# Y1BVER2_0.net
KiCad netlist of a schematic drawn in Altium Designer
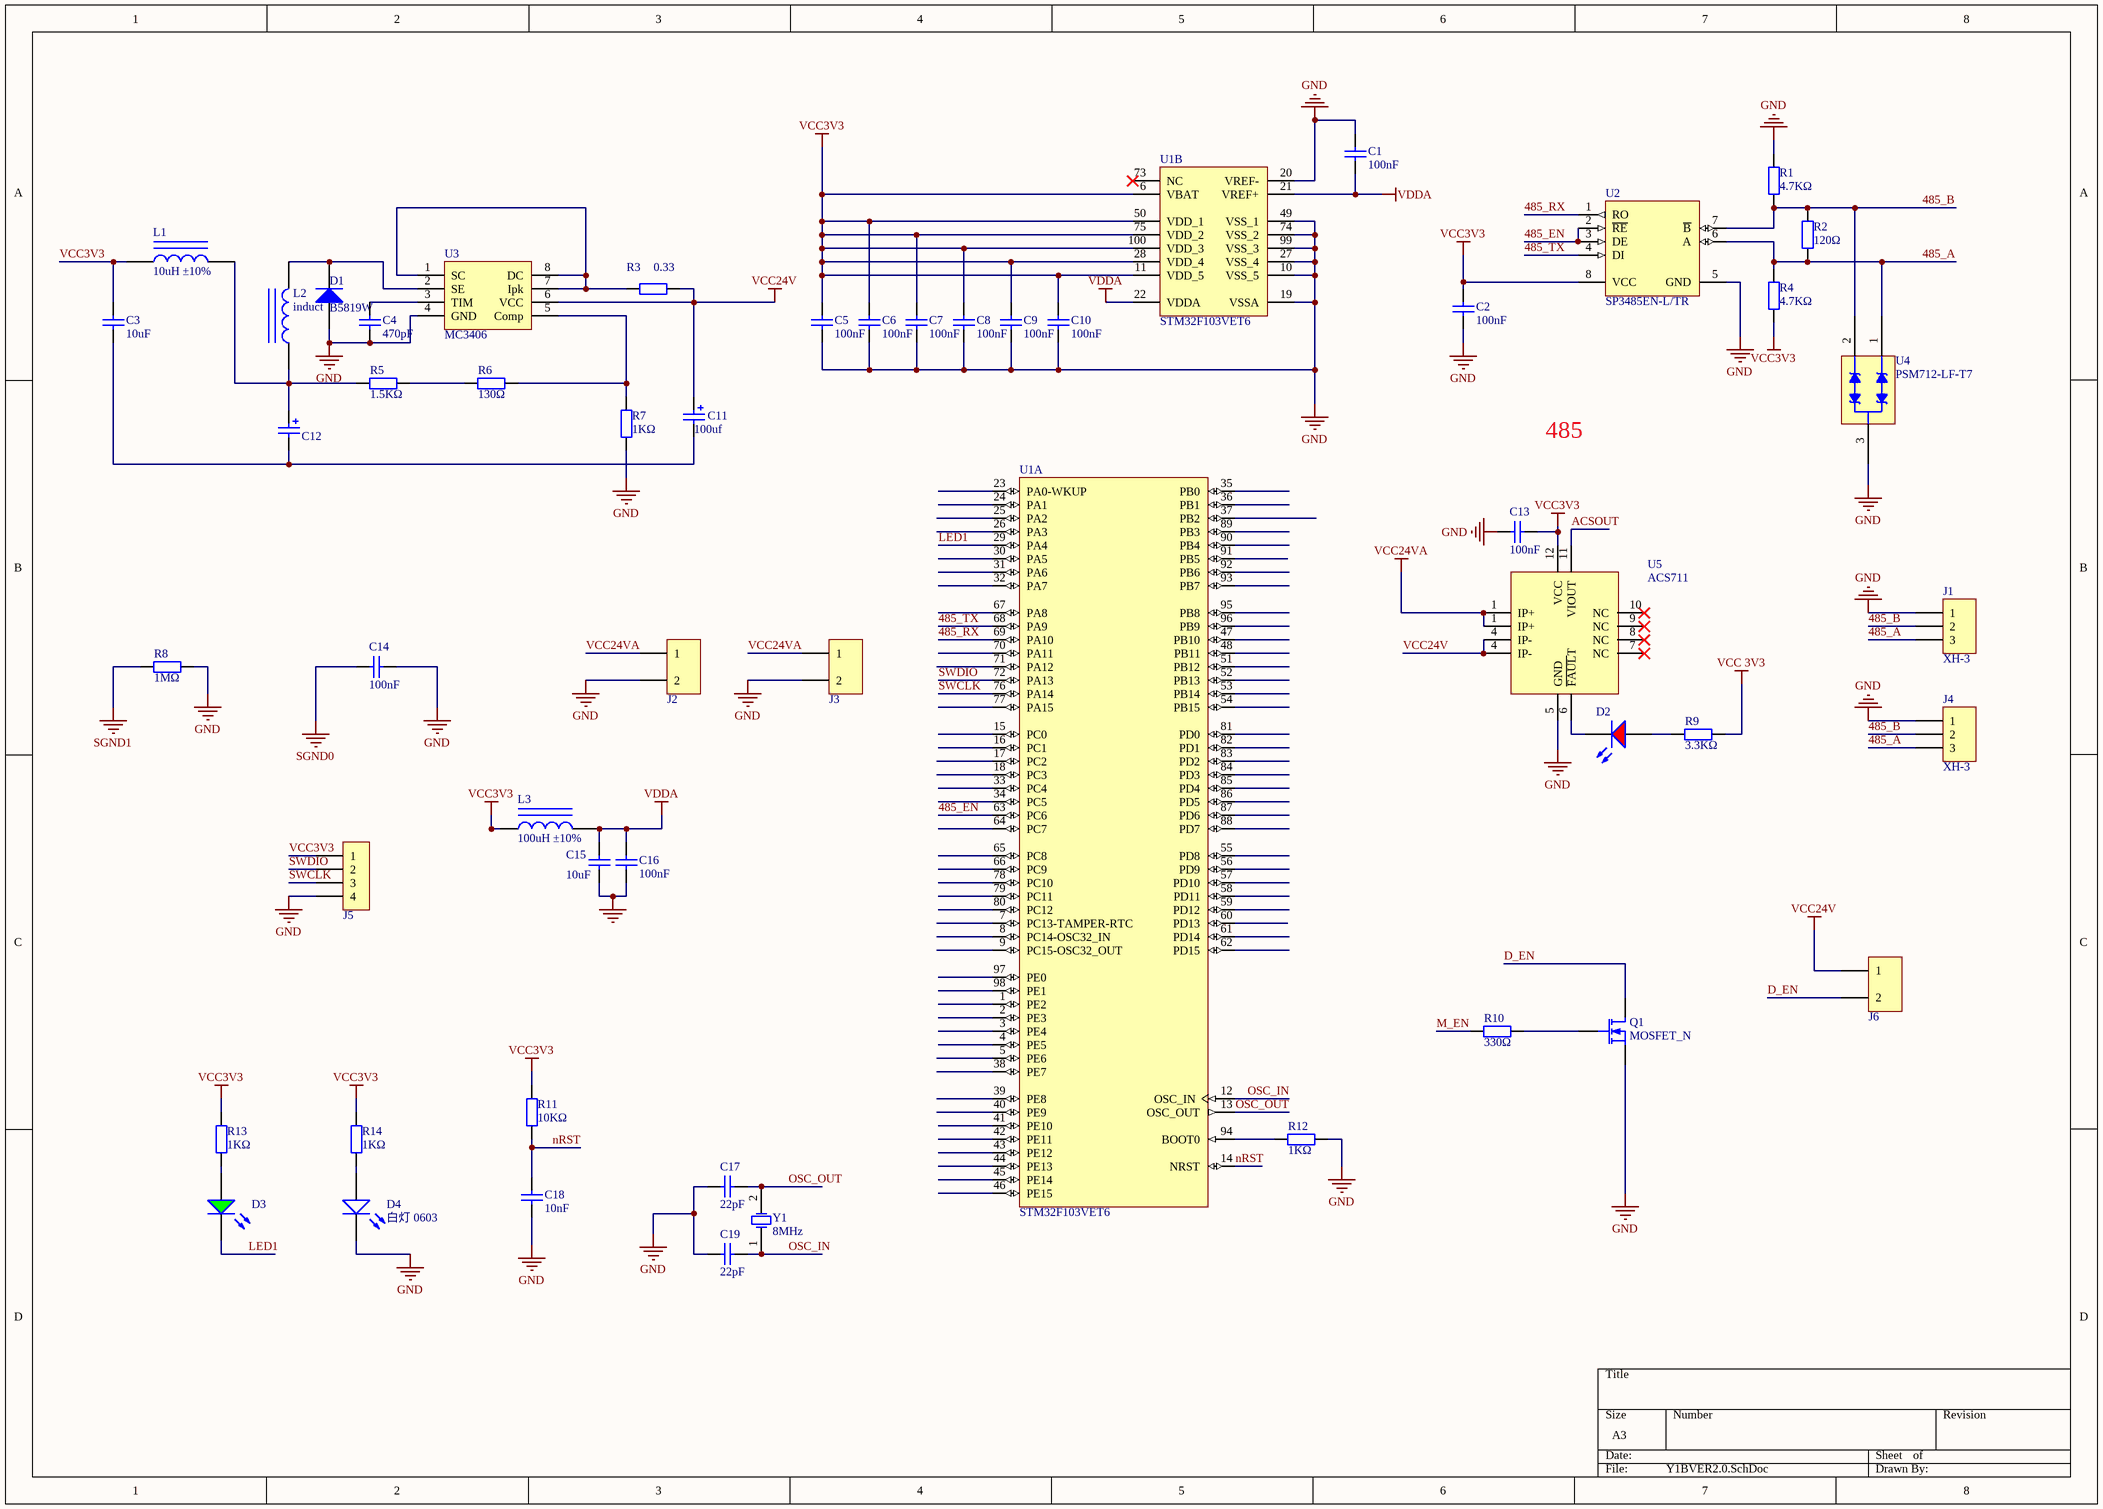
[diagram p0: Y1BVER2.0.SchDoc]

(export (version "E")
  (design (tool "Eeschema 10.0.6"))
  (components
    (comp (ref "C1")
      (value "100nF")
      (footprint "0603_C")
      (description "贴片电容")
      (libsource (lib "AD封装2018.9.19Miscellaneous Devices LC") (part "0603 100nF (104) 10% 50V"))
    )
    (comp (ref "C2")
      (value "100nF")
      (footprint "0603_C")
      (description "贴片电容")
      (libsource (lib "AD封装2018.9.19Miscellaneous Devices LC") (part "0603 100nF (104) 10% 50V"))
    )
    (comp (ref "C3")
      (value "10uF")
      (footprint "0603_C")
      (description "贴片电容")
      (libsource (lib "AD封装2018.9.19Miscellaneous Devices LC") (part "0603 10uF (106) 10% 10V"))
    )
    (comp (ref "C4")
      (value "470pF")
      (footprint "0603_C")
      (description "贴片电容")
      (libsource (lib "AD封装2018.9.19Miscellaneous Devices LC") (part "0603 470pF (471) 10% 50V"))
    )
    (comp (ref "C5")
      (value "100nF")
      (footprint "0603_C")
      (description "贴片电容")
      (libsource (lib "AD封装2018.9.19Miscellaneous Devices LC") (part "0603 100nF (104) 10% 50V"))
    )
    (comp (ref "C6")
      (value "100nF")
      (footprint "0603_C")
      (description "贴片电容")
      (libsource (lib "AD封装2018.9.19Miscellaneous Devices LC") (part "0603 100nF (104) 10% 50V"))
    )
    (comp (ref "C7")
      (value "100nF")
      (footprint "0603_C")
      (description "贴片电容")
      (libsource (lib "AD封装2018.9.19Miscellaneous Devices LC") (part "0603 100nF (104) 10% 50V"))
    )
    (comp (ref "C8")
      (value "100nF")
      (footprint "0603_C")
      (description "贴片电容")
      (libsource (lib "AD封装2018.9.19Miscellaneous Devices LC") (part "0603 100nF (104) 10% 50V"))
    )
    (comp (ref "C9")
      (value "100nF")
      (footprint "0603_C")
      (description "贴片电容")
      (libsource (lib "AD封装2018.9.19Miscellaneous Devices LC") (part "0603 100nF (104) 10% 50V"))
    )
    (comp (ref "C10")
      (value "100nF")
      (footprint "0603_C")
      (description "贴片电容")
      (libsource (lib "AD封装2018.9.19Miscellaneous Devices LC") (part "0603 100nF (104) 10% 50V"))
    )
    (comp (ref "C11") (value "100uf") (footprint "E_6.3*5.4") (libsource (lib "我的集成库") (part "C")))
    (comp (ref "C12") (value "C") (footprint "E_6.3*5.4") (libsource (lib "我的集成库") (part "C")))
    (comp (ref "C13")
      (value "100nF")
      (footprint "0603_C")
      (description "贴片电容")
      (libsource (lib "AD封装2018.9.19Miscellaneous Devices LC") (part "0603 100nF (104) 10% 50V"))
    )
    (comp (ref "C14")
      (value "100nF")
      (footprint "0603_C")
      (description "贴片电容")
      (libsource (lib "AD封装2018.9.19Miscellaneous Devices LC") (part "0603 100nF (104) 10% 50V"))
    )
    (comp (ref "C15")
      (value "10uF")
      (footprint "0603_C")
      (description "贴片电容")
      (libsource (lib "AD封装2018.9.19Miscellaneous Devices LC") (part "0603 10uF (106) 10% 10V"))
    )
    (comp (ref "C16")
      (value "100nF")
      (footprint "0603_C")
      (description "贴片电容")
      (libsource (lib "AD封装2018.9.19Miscellaneous Devices LC") (part "0603 100nF (104) 10% 50V"))
    )
    (comp (ref "C17")
      (value "22pF")
      (footprint "0603_C")
      (description "贴片电容")
      (libsource (lib "Cap") (part "0603 22pF (220) 5% 50V"))
    )
    (comp (ref "C18")
      (value "10nF")
      (footprint "0603_C")
      (description "贴片电容")
      (libsource (lib "AD封装2018.9.19Miscellaneous Devices LC") (part "0603 10nF (103) 10% 50V"))
    )
    (comp (ref "C19")
      (value "22pF")
      (footprint "0603_C")
      (description "贴片电容")
      (libsource (lib "Cap") (part "0603 22pF (220) 5% 50V"))
    )
    (comp (ref "D1")
      (value "B5819W")
      (footprint "SOD-123")
      (description "肖特基二极管")
      (libsource (lib "Diode") (part "SOD-123 B5819W  SL"))
    )
    (comp (ref "D2")
      (value "~")
      (footprint "0603_LED_S1")
      (description "发光二极管")
      (libsource (lib "AD封装2018.9.19Miscellaneous Devices LC") (part "0603 红灯"))
    )
    (comp (ref "D3")
      (value "绿灯 0603")
      (footprint "0603_LED_S1")
      (description "发光二极管")
      (libsource (lib "AD封装2018.9.19Miscellaneous Devices LC") (part "0603 绿灯"))
    )
    (comp (ref "D4")
      (value "白灯 0603")
      (footprint "0603_LED_S1")
      (description "发光二极管")
      (libsource (lib "AD封装2018.9.19Miscellaneous Devices LC") (part "0603 白灯"))
    )
    (comp (ref "J1") (value "XH-3") (footprint "ph3-2.0") (libsource (lib "我的原理图库") (part "XH-3")))
    (comp (ref "J2") (value "MOTOR") (footprint "5557_a") (libsource (lib "我的集成库") (part "header2")))
    (comp (ref "J3") (value "MOTOR") (footprint "5557_a") (libsource (lib "我的集成库") (part "header2")))
    (comp (ref "J4") (value "XH-3") (footprint "ph3-2.0") (libsource (lib "我的原理图库") (part "XH-3")))
    (comp (ref "J5") (value "header4") (footprint "xh-4") (libsource (lib "我的原理图库") (part "header4")))
    (comp (ref "J6") (value "MOTOR") (footprint "5557_a") (libsource (lib "我的原理图库") (part "header2")))
    (comp (ref "L1")
      (value "10uH ±10%")
      (footprint "0603_L")
      (description "贴片电感")
      (libsource (lib "AD封装2018.9.19Miscellaneous Devices LC") (part "0603 10uH 10%"))
    )
    (comp (ref "L2") (value "induct") (footprint "L-5*5*4") (libsource (lib "我的集成库") (part "induct")))
    (comp (ref "L3")
      (value "100uH ±10%")
      (footprint "0805_L")
      (description "贴片电感")
      (libsource (lib "IUD") (part "0805 100uH 10%"))
    )
    (comp (ref "Q1") (value "MOSFET_N") (footprint "TO-252-2") (libsource (lib "我的集成库") (part "MOSFET_N")))
    (comp (ref "R1")
      (value "4.7KΩ")
      (footprint "0603_R")
      (description "贴片电阻")
      (libsource (lib "AD封装2018.9.19Miscellaneous Devices LC") (part "0603 4.7KΩ (4701) 1%"))
    )
    (comp (ref "R2")
      (value "120Ω")
      (footprint "0603_R")
      (description "贴片电阻")
      (libsource (lib "AD封装2018.9.19Miscellaneous Devices LC") (part "0603 120Ω (1200) 1%"))
    )
    (comp (ref "R3")
      (value "0.33")
      (footprint "0603_R")
      (description "贴片电阻")
      (libsource (lib "") (part "0603 1KΩ (1001) 1%_1"))
    )
    (comp (ref "R4")
      (value "4.7KΩ")
      (footprint "0603_R")
      (description "贴片电阻")
      (libsource (lib "AD封装2018.9.19Miscellaneous Devices LC") (part "0603 4.7KΩ (4701) 1%"))
    )
    (comp (ref "R5")
      (value "1.5KΩ")
      (footprint "0603_R")
      (description "贴片电阻")
      (libsource (lib "AD封装2018.9.19Miscellaneous Devices LC") (part "0603 1.5KΩ (1501) 1%"))
    )
    (comp (ref "R6")
      (value "130Ω")
      (footprint "0603_R")
      (description "贴片电阻")
      (libsource (lib "AD封装2018.9.19Miscellaneous Devices LC") (part "0603 130Ω (1300) 1%"))
    )
    (comp (ref "R7")
      (value "1KΩ")
      (footprint "0603_R")
      (description "贴片电阻")
      (libsource (lib "AD封装2018.9.19Miscellaneous Devices LC") (part "0603 1KΩ (1001) 1%"))
    )
    (comp (ref "R8")
      (value "1MΩ")
      (footprint "0603_R")
      (description "贴片电阻")
      (libsource (lib "AD封装2018.9.19Miscellaneous Devices LC") (part "0603 1MΩ (1004) 1%"))
    )
    (comp (ref "R9")
      (value "3.3KΩ")
      (footprint "0603_R")
      (description "贴片电阻")
      (libsource (lib "AD封装2018.9.19Miscellaneous Devices LC") (part "0603 3.3KΩ (3301) 1%"))
    )
    (comp (ref "R10")
      (value "330Ω")
      (footprint "0603_R")
      (description "贴片电阻")
      (libsource (lib "AD封装2018.9.19Miscellaneous Devices LC") (part "0603 330Ω (3300) 1%"))
    )
    (comp (ref "R11")
      (value "10KΩ")
      (footprint "0603_R")
      (description "贴片电阻")
      (libsource (lib "AD封装2018.9.19Miscellaneous Devices LC") (part "0603 10KΩ (1002) 1%"))
    )
    (comp (ref "R12")
      (value "1KΩ")
      (footprint "0603_R")
      (description "贴片电阻")
      (libsource (lib "") (part "0603 1KΩ (1001) 1%_1"))
    )
    (comp (ref "R13")
      (value "1KΩ")
      (footprint "0603_R")
      (description "贴片电阻")
      (libsource (lib "AD封装2018.9.19Miscellaneous Devices LC") (part "0603 1KΩ (1001) 1%"))
    )
    (comp (ref "R14")
      (value "1KΩ")
      (footprint "0603_R")
      (description "贴片电阻")
      (libsource (lib "AD封装2018.9.19Miscellaneous Devices LC") (part "0603 1KΩ (1001) 1%"))
    )
    (comp (ref "U1")
      (value "STM32F103VET6")
      (footprint "LQFP-100_14x14x05P")
      (description "ARM")
      (libsource (lib "AD封装2018.9.19Miscellaneous Devices LC") (part "STM32F103VET6"))
    )
    (comp (ref "U2")
      (value "SP3485EN-L/TR")
      (footprint "SOIC-8_150mil")
      (description "RS-485/RS-422")
      (libsource (lib "IC") (part "SP3485EN-L/TR_[C8963]"))
    )
    (comp (ref "U3")
      (value "MC3406")
      (footprint "SOP-8_150mil")
      (libsource (lib "我的集成库") (part "MC3406_DCDC"))
    )
    (comp (ref "U4")
      (value "PSM712-LF-T7")
      (footprint "SOT-23(SOT-23-3)")
      (description "TVS")
      (libsource (lib "AD封装2018.9.19Miscellaneous Devices LC") (part "PSM712-LF-T7_[C32677]"))
    )
    (comp (ref "U5") (value "ACS711") (footprint "ACS711") (libsource (lib "我的原理图库") (part "ACS711电流传感器")))
    (comp (ref "Y1")
      (value "8MHz")
      (footprint "SMD-5032_2P")
      (description "贴片晶振")
      (libsource (lib "CrystalOscillator") (part "SMD-5032_2P 8MHz 20ppm 20pF"))
    )
  )
  (nets
    (net (code "1") (name "/485_A") (class "Default")
      (node (ref "J1") (pin "3") (pinfunction "3_3") (pintype "passive"))
      (node (ref "J4") (pin "3") (pinfunction "3_3") (pintype "passive"))
      (node (ref "R2") (pin "2") (pinfunction "2_2") (pintype "passive"))
      (node (ref "R4") (pin "2") (pinfunction "2_2") (pintype "passive"))
      (node (ref "U2") (pin "6") (pinfunction "A_6") (pintype "bidirectional"))
      (node (ref "U4") (pin "1") (pinfunction "1_1") (pintype "passive"))
    )
    (net (code "2") (name "/485_B") (class "Default")
      (node (ref "J1") (pin "2") (pinfunction "2_2") (pintype "passive"))
      (node (ref "J4") (pin "2") (pinfunction "2_2") (pintype "passive"))
      (node (ref "R1") (pin "1") (pinfunction "1_1") (pintype "passive"))
      (node (ref "R2") (pin "1") (pinfunction "1_1") (pintype "passive"))
      (node (ref "U2") (pin "7") (pinfunction "~{B}_7") (pintype "bidirectional"))
      (node (ref "U4") (pin "2") (pinfunction "2_2") (pintype "passive"))
    )
    (net (code "3") (name "/485_EN") (class "Default")
      (node (ref "U1") (pin "63") (pinfunction "PC6_63") (pintype "bidirectional"))
      (node (ref "U2") (pin "2") (pinfunction "~{RE}_2") (pintype "input"))
      (node (ref "U2") (pin "3") (pinfunction "DE_3") (pintype "input"))
    )
    (net (code "4") (name "/485_RX") (class "Default")
      (node (ref "U1") (pin "69") (pinfunction "PA10_69") (pintype "bidirectional"))
      (node (ref "U2") (pin "1") (pinfunction "RO_1") (pintype "output"))
    )
    (net (code "5") (name "/485_TX") (class "Default")
      (node (ref "U1") (pin "68") (pinfunction "PA9_68") (pintype "bidirectional"))
      (node (ref "U2") (pin "4") (pinfunction "DI_4") (pintype "input"))
    )
    (net (code "6") (name "/ACSOUT") (class "Default")
      (node (ref "U5") (pin "11") (pinfunction "VIOUT_11") (pintype "passive"))
    )
    (net (code "7") (name "/D_EN") (class "Default")
      (node (ref "J6") (pin "2") (pinfunction "2_2") (pintype "passive"))
      (node (ref "Q1") (pin "2") (pinfunction "D_2") (pintype "passive"))
    )
    (net (code "8") (name "/LED1") (class "Default")
      (node (ref "D3") (pin "K") (pinfunction "K_K") (pintype "passive"))
      (node (ref "U1") (pin "29") (pinfunction "PA4_29") (pintype "bidirectional"))
    )
    (net (code "9") (name "/M_EN") (class "Default")
      (node (ref "R10") (pin "1") (pinfunction "1_1") (pintype "passive"))
    )
    (net (code "10") (name "/OSC_IN") (class "Default")
      (node (ref "C19") (pin "2") (pinfunction "2_2") (pintype "passive"))
      (node (ref "U1") (pin "12") (pinfunction "OSC_IN_12") (pintype "input"))
      (node (ref "Y1") (pin "1") (pinfunction "OSC1_1") (pintype "passive"))
    )
    (net (code "11") (name "/OSC_OUT") (class "Default")
      (node (ref "C17") (pin "2") (pinfunction "2_2") (pintype "passive"))
      (node (ref "U1") (pin "13") (pinfunction "OSC_OUT_13") (pintype "output"))
      (node (ref "Y1") (pin "2") (pinfunction "OSC2_2") (pintype "passive"))
    )
    (net (code "12") (name "/SWCLK") (class "Default")
      (node (ref "J5") (pin "3") (pinfunction "3_3") (pintype "passive"))
      (node (ref "U1") (pin "76") (pinfunction "PA14_76") (pintype "bidirectional"))
    )
    (net (code "13") (name "/SWDIO") (class "Default")
      (node (ref "J5") (pin "2") (pinfunction "2_2") (pintype "passive"))
      (node (ref "U1") (pin "72") (pinfunction "PA13_72") (pintype "bidirectional"))
    )
    (net (code "14") (name "/nRST") (class "Default")
      (node (ref "C18") (pin "2") (pinfunction "2_2") (pintype "passive"))
      (node (ref "R11") (pin "1") (pinfunction "1_1") (pintype "passive"))
      (node (ref "U1") (pin "14") (pinfunction "NRST_14") (pintype "bidirectional"))
    )
    (net (code "15") (name "GND") (class "Default")
      (node (ref "C1") (pin "1") (pinfunction "1_1") (pintype "passive"))
      (node (ref "C10") (pin "1") (pinfunction "1_1") (pintype "passive"))
      (node (ref "C13") (pin "2") (pinfunction "2_2") (pintype "passive"))
      (node (ref "C14") (pin "2") (pinfunction "2_2") (pintype "passive"))
      (node (ref "C15") (pin "1") (pinfunction "1_1") (pintype "passive"))
      (node (ref "C16") (pin "1") (pinfunction "1_1") (pintype "passive"))
      (node (ref "C17") (pin "1") (pinfunction "1_1") (pintype "passive"))
      (node (ref "C18") (pin "1") (pinfunction "1_1") (pintype "passive"))
      (node (ref "C19") (pin "1") (pinfunction "1_1") (pintype "passive"))
      (node (ref "C2") (pin "2") (pinfunction "2_2") (pintype "passive"))
      (node (ref "C4") (pin "2") (pinfunction "2_2") (pintype "passive"))
      (node (ref "C5") (pin "1") (pinfunction "1_1") (pintype "passive"))
      (node (ref "C6") (pin "1") (pinfunction "1_1") (pintype "passive"))
      (node (ref "C7") (pin "1") (pinfunction "1_1") (pintype "passive"))
      (node (ref "C8") (pin "1") (pinfunction "1_1") (pintype "passive"))
      (node (ref "C9") (pin "1") (pinfunction "1_1") (pintype "passive"))
      (node (ref "D1") (pin "1") (pinfunction "A_1") (pintype "passive"))
      (node (ref "D4") (pin "K") (pinfunction "K_K") (pintype "passive"))
      (node (ref "J1") (pin "1") (pinfunction "1_1") (pintype "passive"))
      (node (ref "J2") (pin "2") (pinfunction "2_2") (pintype "passive"))
      (node (ref "J3") (pin "2") (pinfunction "2_2") (pintype "passive"))
      (node (ref "J4") (pin "1") (pinfunction "1_1") (pintype "passive"))
      (node (ref "J5") (pin "4") (pinfunction "4_4") (pintype "passive"))
      (node (ref "Q1") (pin "3") (pinfunction "S_3") (pintype "passive"))
      (node (ref "R1") (pin "2") (pinfunction "2_2") (pintype "passive"))
      (node (ref "R12") (pin "2") (pinfunction "2_2") (pintype "passive"))
      (node (ref "R7") (pin "1") (pinfunction "1_1") (pintype "passive"))
      (node (ref "R8") (pin "2") (pinfunction "2_2") (pintype "passive"))
      (node (ref "U1") (pin "10") (pinfunction "VSS_5_10") (pintype "power_in"))
      (node (ref "U1") (pin "19") (pinfunction "VSSA_19") (pintype "power_in"))
      (node (ref "U1") (pin "20") (pinfunction "VREF-_20") (pintype "power_in"))
      (node (ref "U1") (pin "27") (pinfunction "VSS_4_27") (pintype "power_in"))
      (node (ref "U1") (pin "49") (pinfunction "VSS_1_49") (pintype "power_in"))
      (node (ref "U1") (pin "74") (pinfunction "VSS_2_74") (pintype "power_in"))
      (node (ref "U1") (pin "99") (pinfunction "VSS_3_99") (pintype "power_in"))
      (node (ref "U2") (pin "5") (pinfunction "GND_5") (pintype "power_in"))
      (node (ref "U3") (pin "4") (pinfunction "GND_4") (pintype "passive"))
      (node (ref "U4") (pin "3") (pinfunction "3_3") (pintype "passive"))
      (node (ref "U5") (pin "5") (pinfunction "GND_5") (pintype "passive"))
    )
    (net (code "16") (name "Net-(C11-Pad2)") (class "Default")
      (node (ref "C11") (pin "2") (pinfunction "2_2") (pintype "passive"))
      (node (ref "C12") (pin "2") (pinfunction "2_2") (pintype "passive"))
      (node (ref "C3") (pin "1") (pinfunction "1_1") (pintype "passive"))
    )
    (net (code "17") (name "Net-(C12-Pad1)") (class "Default")
      (node (ref "C12") (pin "1") (pinfunction "1_1") (pintype "passive"))
      (node (ref "L1") (pin "2") (pinfunction "2_2") (pintype "passive"))
      (node (ref "L2") (pin "1") (pinfunction "1_1") (pintype "passive"))
      (node (ref "R5") (pin "1") (pinfunction "1_1") (pintype "passive"))
    )
    (net (code "18") (name "Net-(D1-K)") (class "Default")
      (node (ref "D1") (pin "2") (pinfunction "K_2") (pintype "passive"))
      (node (ref "L2") (pin "2") (pinfunction "2_2") (pintype "passive"))
      (node (ref "U3") (pin "2") (pinfunction "SE_2") (pintype "passive"))
    )
    (net (code "19") (name "Net-(D2-PadA)") (class "Default")
      (node (ref "D2") (pin "A") (pinfunction "A_A") (pintype "passive"))
      (node (ref "R9") (pin "1") (pinfunction "1_1") (pintype "passive"))
    )
    (net (code "20") (name "Net-(D3-PadA)") (class "Default")
      (node (ref "D3") (pin "A") (pinfunction "A_A") (pintype "passive"))
      (node (ref "R13") (pin "1") (pinfunction "1_1") (pintype "passive"))
    )
    (net (code "21") (name "Net-(D4-PadA)") (class "Default")
      (node (ref "D4") (pin "A") (pinfunction "A_A") (pintype "passive"))
      (node (ref "R14") (pin "1") (pinfunction "1_1") (pintype "passive"))
    )
    (net (code "22") (name "Net-(Q1-G)") (class "Default")
      (node (ref "Q1") (pin "1") (pinfunction "G_1") (pintype "passive"))
      (node (ref "R10") (pin "2") (pinfunction "2_2") (pintype "passive"))
    )
    (net (code "23") (name "Net-(R5-Pad2)") (class "Default")
      (node (ref "R5") (pin "2") (pinfunction "2_2") (pintype "passive"))
      (node (ref "R6") (pin "1") (pinfunction "1_1") (pintype "passive"))
    )
    (net (code "24") (name "Net-(U1A-BOOT0)") (class "Default")
      (node (ref "R12") (pin "1") (pinfunction "1_1") (pintype "passive"))
      (node (ref "U1") (pin "94") (pinfunction "BOOT0_94") (pintype "input"))
    )
    (net (code "25") (name "Net-(U3-Comp)") (class "Default")
      (node (ref "R6") (pin "2") (pinfunction "2_2") (pintype "passive"))
      (node (ref "R7") (pin "2") (pinfunction "2_2") (pintype "passive"))
      (node (ref "U3") (pin "5") (pinfunction "Comp_5") (pintype "passive"))
    )
    (net (code "26") (name "Net-(U3-DC)") (class "Default")
      (node (ref "R3") (pin "1") (pinfunction "1_1") (pintype "passive"))
      (node (ref "U3") (pin "1") (pinfunction "SC_1") (pintype "passive"))
      (node (ref "U3") (pin "7") (pinfunction "Ipk_7") (pintype "passive"))
      (node (ref "U3") (pin "8") (pinfunction "DC_8") (pintype "passive"))
    )
    (net (code "27") (name "Net-(U3-TIM)") (class "Default")
      (node (ref "C4") (pin "1") (pinfunction "1_1") (pintype "passive"))
      (node (ref "U3") (pin "3") (pinfunction "TIM_3") (pintype "passive"))
    )
    (net (code "28") (name "Net-(U5-~{FAUL}T)") (class "Default")
      (node (ref "D2") (pin "K") (pinfunction "K_K") (pintype "passive"))
      (node (ref "U5") (pin "6") (pinfunction "~{FAUL}T_6") (pintype "passive"))
    )
    (net (code "29") (name "SGND0") (class "Default")
      (node (ref "C14") (pin "1") (pinfunction "1_1") (pintype "passive"))
    )
    (net (code "30") (name "SGND1") (class "Default")
      (node (ref "R8") (pin "1") (pinfunction "1_1") (pintype "passive"))
    )
    (net (code "31") (name "VCC 3V3") (class "Default")
      (node (ref "R9") (pin "2") (pinfunction "2_2") (pintype "passive"))
    )
    (net (code "32") (name "VCC3V3") (class "Default")
      (node (ref "C10") (pin "2") (pinfunction "2_2") (pintype "passive"))
      (node (ref "C13") (pin "1") (pinfunction "1_1") (pintype "passive"))
      (node (ref "C2") (pin "1") (pinfunction "1_1") (pintype "passive"))
      (node (ref "C3") (pin "2") (pinfunction "2_2") (pintype "passive"))
      (node (ref "C5") (pin "2") (pinfunction "2_2") (pintype "passive"))
      (node (ref "C6") (pin "2") (pinfunction "2_2") (pintype "passive"))
      (node (ref "C7") (pin "2") (pinfunction "2_2") (pintype "passive"))
      (node (ref "C8") (pin "2") (pinfunction "2_2") (pintype "passive"))
      (node (ref "C9") (pin "2") (pinfunction "2_2") (pintype "passive"))
      (node (ref "J5") (pin "1") (pinfunction "1_1") (pintype "passive"))
      (node (ref "L1") (pin "1") (pinfunction "1_1") (pintype "passive"))
      (node (ref "L3") (pin "1") (pinfunction "1_1") (pintype "passive"))
      (node (ref "R11") (pin "2") (pinfunction "2_2") (pintype "passive"))
      (node (ref "R13") (pin "2") (pinfunction "2_2") (pintype "passive"))
      (node (ref "R14") (pin "2") (pinfunction "2_2") (pintype "passive"))
      (node (ref "R4") (pin "1") (pinfunction "1_1") (pintype "passive"))
      (node (ref "U1") (pin "100") (pinfunction "VDD_3_100") (pintype "power_in"))
      (node (ref "U1") (pin "11") (pinfunction "VDD_5_11") (pintype "power_in"))
      (node (ref "U1") (pin "28") (pinfunction "VDD_4_28") (pintype "power_in"))
      (node (ref "U1") (pin "50") (pinfunction "VDD_1_50") (pintype "power_in"))
      (node (ref "U1") (pin "6") (pinfunction "VBAT_6") (pintype "power_in"))
      (node (ref "U1") (pin "75") (pinfunction "VDD_2_75") (pintype "power_in"))
      (node (ref "U2") (pin "8") (pinfunction "VCC_8") (pintype "power_in"))
      (node (ref "U5") (pin "12") (pinfunction "VCC_12") (pintype "passive"))
    )
    (net (code "33") (name "VCC24V") (class "Default")
      (node (ref "C11") (pin "1") (pinfunction "1_1") (pintype "passive"))
      (node (ref "J6") (pin "1") (pinfunction "1_1") (pintype "passive"))
      (node (ref "R3") (pin "2") (pinfunction "2_2") (pintype "passive"))
      (node (ref "U3") (pin "6") (pinfunction "VCC_6") (pintype "passive"))
      (node (ref "U5") (pin "4") (pinfunction "IP-_4") (pintype "passive"))
    )
    (net (code "34") (name "VCC24VA") (class "Default")
      (node (ref "J2") (pin "1") (pinfunction "1_1") (pintype "passive"))
      (node (ref "J3") (pin "1") (pinfunction "1_1") (pintype "passive"))
      (node (ref "U5") (pin "1") (pinfunction "IP+_1") (pintype "passive"))
    )
    (net (code "35") (name "VDDA") (class "Default")
      (node (ref "C1") (pin "2") (pinfunction "2_2") (pintype "passive"))
      (node (ref "C15") (pin "2") (pinfunction "2_2") (pintype "passive"))
      (node (ref "C16") (pin "2") (pinfunction "2_2") (pintype "passive"))
      (node (ref "L3") (pin "2") (pinfunction "2_2") (pintype "passive"))
      (node (ref "U1") (pin "21") (pinfunction "VREF+_21") (pintype "power_in"))
      (node (ref "U1") (pin "22") (pinfunction "VDDA_22") (pintype "power_in"))
    )
    (net (code "36") (name "unconnected-(U1A-PA0-WKUP-Pad23)") (class "Default")
      (node (ref "U1") (pin "23") (pinfunction "PA0-WKUP_23") (pintype "bidirectional"))
    )
    (net (code "37") (name "unconnected-(U1A-PA1-Pad24)") (class "Default")
      (node (ref "U1") (pin "24") (pinfunction "PA1_24") (pintype "bidirectional"))
    )
    (net (code "38") (name "unconnected-(U1A-PA2-Pad25)") (class "Default")
      (node (ref "U1") (pin "25") (pinfunction "PA2_25") (pintype "bidirectional"))
    )
    (net (code "39") (name "unconnected-(U1A-PA3-Pad26)") (class "Default")
      (node (ref "U1") (pin "26") (pinfunction "PA3_26") (pintype "bidirectional"))
    )
    (net (code "40") (name "unconnected-(U1A-PA5-Pad30)") (class "Default")
      (node (ref "U1") (pin "30") (pinfunction "PA5_30") (pintype "bidirectional"))
    )
    (net (code "41") (name "unconnected-(U1A-PA6-Pad31)") (class "Default")
      (node (ref "U1") (pin "31") (pinfunction "PA6_31") (pintype "bidirectional"))
    )
    (net (code "42") (name "unconnected-(U1A-PA7-Pad32)") (class "Default")
      (node (ref "U1") (pin "32") (pinfunction "PA7_32") (pintype "bidirectional"))
    )
    (net (code "43") (name "unconnected-(U1A-PA8-Pad67)") (class "Default")
      (node (ref "U1") (pin "67") (pinfunction "PA8_67") (pintype "bidirectional"))
    )
    (net (code "44") (name "unconnected-(U1A-PA11-Pad70)") (class "Default")
      (node (ref "U1") (pin "70") (pinfunction "PA11_70") (pintype "bidirectional"))
    )
    (net (code "45") (name "unconnected-(U1A-PA12-Pad71)") (class "Default")
      (node (ref "U1") (pin "71") (pinfunction "PA12_71") (pintype "bidirectional"))
    )
    (net (code "46") (name "unconnected-(U1A-PA15-Pad77)") (class "Default")
      (node (ref "U1") (pin "77") (pinfunction "PA15_77") (pintype "bidirectional"))
    )
    (net (code "47") (name "unconnected-(U1A-PB0-Pad35)") (class "Default")
      (node (ref "U1") (pin "35") (pinfunction "PB0_35") (pintype "bidirectional"))
    )
    (net (code "48") (name "unconnected-(U1A-PB1-Pad36)") (class "Default")
      (node (ref "U1") (pin "36") (pinfunction "PB1_36") (pintype "bidirectional"))
    )
    (net (code "49") (name "unconnected-(U1A-PB2-Pad37)") (class "Default")
      (node (ref "U1") (pin "37") (pinfunction "PB2_37") (pintype "bidirectional"))
    )
    (net (code "50") (name "unconnected-(U1A-PB3-Pad89)") (class "Default")
      (node (ref "U1") (pin "89") (pinfunction "PB3_89") (pintype "bidirectional"))
    )
    (net (code "51") (name "unconnected-(U1A-PB4-Pad90)") (class "Default")
      (node (ref "U1") (pin "90") (pinfunction "PB4_90") (pintype "bidirectional"))
    )
    (net (code "52") (name "unconnected-(U1A-PB5-Pad91)") (class "Default")
      (node (ref "U1") (pin "91") (pinfunction "PB5_91") (pintype "bidirectional"))
    )
    (net (code "53") (name "unconnected-(U1A-PB6-Pad92)") (class "Default")
      (node (ref "U1") (pin "92") (pinfunction "PB6_92") (pintype "bidirectional"))
    )
    (net (code "54") (name "unconnected-(U1A-PB7-Pad93)") (class "Default")
      (node (ref "U1") (pin "93") (pinfunction "PB7_93") (pintype "bidirectional"))
    )
    (net (code "55") (name "unconnected-(U1A-PB8-Pad95)") (class "Default")
      (node (ref "U1") (pin "95") (pinfunction "PB8_95") (pintype "bidirectional"))
    )
    (net (code "56") (name "unconnected-(U1A-PB9-Pad96)") (class "Default")
      (node (ref "U1") (pin "96") (pinfunction "PB9_96") (pintype "bidirectional"))
    )
    (net (code "57") (name "unconnected-(U1A-PB10-Pad47)") (class "Default")
      (node (ref "U1") (pin "47") (pinfunction "PB10_47") (pintype "bidirectional"))
    )
    (net (code "58") (name "unconnected-(U1A-PB11-Pad48)") (class "Default")
      (node (ref "U1") (pin "48") (pinfunction "PB11_48") (pintype "bidirectional"))
    )
    (net (code "59") (name "unconnected-(U1A-PB12-Pad51)") (class "Default")
      (node (ref "U1") (pin "51") (pinfunction "PB12_51") (pintype "bidirectional"))
    )
    (net (code "60") (name "unconnected-(U1A-PB13-Pad52)") (class "Default")
      (node (ref "U1") (pin "52") (pinfunction "PB13_52") (pintype "bidirectional"))
    )
    (net (code "61") (name "unconnected-(U1A-PB14-Pad53)") (class "Default")
      (node (ref "U1") (pin "53") (pinfunction "PB14_53") (pintype "bidirectional"))
    )
    (net (code "62") (name "unconnected-(U1A-PB15-Pad54)") (class "Default")
      (node (ref "U1") (pin "54") (pinfunction "PB15_54") (pintype "bidirectional"))
    )
    (net (code "63") (name "unconnected-(U1A-PC0-Pad15)") (class "Default")
      (node (ref "U1") (pin "15") (pinfunction "PC0_15") (pintype "bidirectional"))
    )
    (net (code "64") (name "unconnected-(U1A-PC1-Pad16)") (class "Default")
      (node (ref "U1") (pin "16") (pinfunction "PC1_16") (pintype "bidirectional"))
    )
    (net (code "65") (name "unconnected-(U1A-PC2-Pad17)") (class "Default")
      (node (ref "U1") (pin "17") (pinfunction "PC2_17") (pintype "bidirectional"))
    )
    (net (code "66") (name "unconnected-(U1A-PC3-Pad18)") (class "Default")
      (node (ref "U1") (pin "18") (pinfunction "PC3_18") (pintype "bidirectional"))
    )
    (net (code "67") (name "unconnected-(U1A-PC4-Pad33)") (class "Default")
      (node (ref "U1") (pin "33") (pinfunction "PC4_33") (pintype "bidirectional"))
    )
    (net (code "68") (name "unconnected-(U1A-PC5-Pad34)") (class "Default")
      (node (ref "U1") (pin "34") (pinfunction "PC5_34") (pintype "bidirectional"))
    )
    (net (code "69") (name "unconnected-(U1A-PC7-Pad64)") (class "Default")
      (node (ref "U1") (pin "64") (pinfunction "PC7_64") (pintype "bidirectional"))
    )
    (net (code "70") (name "unconnected-(U1A-PC8-Pad65)") (class "Default")
      (node (ref "U1") (pin "65") (pinfunction "PC8_65") (pintype "bidirectional"))
    )
    (net (code "71") (name "unconnected-(U1A-PC9-Pad66)") (class "Default")
      (node (ref "U1") (pin "66") (pinfunction "PC9_66") (pintype "bidirectional"))
    )
    (net (code "72") (name "unconnected-(U1A-PC10-Pad78)") (class "Default")
      (node (ref "U1") (pin "78") (pinfunction "PC10_78") (pintype "bidirectional"))
    )
    (net (code "73") (name "unconnected-(U1A-PC11-Pad79)") (class "Default")
      (node (ref "U1") (pin "79") (pinfunction "PC11_79") (pintype "bidirectional"))
    )
    (net (code "74") (name "unconnected-(U1A-PC12-Pad80)") (class "Default")
      (node (ref "U1") (pin "80") (pinfunction "PC12_80") (pintype "bidirectional"))
    )
    (net (code "75") (name "unconnected-(U1A-PC13-TAMPER-RTC-Pad7)") (class "Default")
      (node (ref "U1") (pin "7") (pinfunction "PC13-TAMPER-RTC_7") (pintype "bidirectional"))
    )
    (net (code "76") (name "unconnected-(U1A-PC14-OSC32_IN-Pad8)") (class "Default")
      (node (ref "U1") (pin "8") (pinfunction "PC14-OSC32_IN_8") (pintype "bidirectional"))
    )
    (net (code "77") (name "unconnected-(U1A-PC15-OSC32_OUT-Pad9)") (class "Default")
      (node (ref "U1") (pin "9") (pinfunction "PC15-OSC32_OUT_9") (pintype "bidirectional"))
    )
    (net (code "78") (name "unconnected-(U1A-PD0-Pad81)") (class "Default")
      (node (ref "U1") (pin "81") (pinfunction "PD0_81") (pintype "bidirectional"))
    )
    (net (code "79") (name "unconnected-(U1A-PD1-Pad82)") (class "Default")
      (node (ref "U1") (pin "82") (pinfunction "PD1_82") (pintype "bidirectional"))
    )
    (net (code "80") (name "unconnected-(U1A-PD2-Pad83)") (class "Default")
      (node (ref "U1") (pin "83") (pinfunction "PD2_83") (pintype "bidirectional"))
    )
    (net (code "81") (name "unconnected-(U1A-PD3-Pad84)") (class "Default")
      (node (ref "U1") (pin "84") (pinfunction "PD3_84") (pintype "bidirectional"))
    )
    (net (code "82") (name "unconnected-(U1A-PD4-Pad85)") (class "Default")
      (node (ref "U1") (pin "85") (pinfunction "PD4_85") (pintype "bidirectional"))
    )
    (net (code "83") (name "unconnected-(U1A-PD5-Pad86)") (class "Default")
      (node (ref "U1") (pin "86") (pinfunction "PD5_86") (pintype "bidirectional"))
    )
    (net (code "84") (name "unconnected-(U1A-PD6-Pad87)") (class "Default")
      (node (ref "U1") (pin "87") (pinfunction "PD6_87") (pintype "bidirectional"))
    )
    (net (code "85") (name "unconnected-(U1A-PD7-Pad88)") (class "Default")
      (node (ref "U1") (pin "88") (pinfunction "PD7_88") (pintype "bidirectional"))
    )
    (net (code "86") (name "unconnected-(U1A-PD8-Pad55)") (class "Default")
      (node (ref "U1") (pin "55") (pinfunction "PD8_55") (pintype "bidirectional"))
    )
    (net (code "87") (name "unconnected-(U1A-PD9-Pad56)") (class "Default")
      (node (ref "U1") (pin "56") (pinfunction "PD9_56") (pintype "bidirectional"))
    )
    (net (code "88") (name "unconnected-(U1A-PD10-Pad57)") (class "Default")
      (node (ref "U1") (pin "57") (pinfunction "PD10_57") (pintype "bidirectional"))
    )
    (net (code "89") (name "unconnected-(U1A-PD11-Pad58)") (class "Default")
      (node (ref "U1") (pin "58") (pinfunction "PD11_58") (pintype "bidirectional"))
    )
    (net (code "90") (name "unconnected-(U1A-PD12-Pad59)") (class "Default")
      (node (ref "U1") (pin "59") (pinfunction "PD12_59") (pintype "bidirectional"))
    )
    (net (code "91") (name "unconnected-(U1A-PD13-Pad60)") (class "Default")
      (node (ref "U1") (pin "60") (pinfunction "PD13_60") (pintype "bidirectional"))
    )
    (net (code "92") (name "unconnected-(U1A-PD14-Pad61)") (class "Default")
      (node (ref "U1") (pin "61") (pinfunction "PD14_61") (pintype "bidirectional"))
    )
    (net (code "93") (name "unconnected-(U1A-PD15-Pad62)") (class "Default")
      (node (ref "U1") (pin "62") (pinfunction "PD15_62") (pintype "bidirectional"))
    )
    (net (code "94") (name "unconnected-(U1A-PE0-Pad97)") (class "Default")
      (node (ref "U1") (pin "97") (pinfunction "PE0_97") (pintype "bidirectional"))
    )
    (net (code "95") (name "unconnected-(U1A-PE1-Pad98)") (class "Default")
      (node (ref "U1") (pin "98") (pinfunction "PE1_98") (pintype "bidirectional"))
    )
    (net (code "96") (name "unconnected-(U1A-PE2-Pad1)") (class "Default")
      (node (ref "U1") (pin "1") (pinfunction "PE2_1") (pintype "bidirectional"))
    )
    (net (code "97") (name "unconnected-(U1A-PE3-Pad2)") (class "Default")
      (node (ref "U1") (pin "2") (pinfunction "PE3_2") (pintype "bidirectional"))
    )
    (net (code "98") (name "unconnected-(U1A-PE4-Pad3)") (class "Default")
      (node (ref "U1") (pin "3") (pinfunction "PE4_3") (pintype "bidirectional"))
    )
    (net (code "99") (name "unconnected-(U1A-PE5-Pad4)") (class "Default")
      (node (ref "U1") (pin "4") (pinfunction "PE5_4") (pintype "bidirectional"))
    )
    (net (code "100") (name "unconnected-(U1A-PE6-Pad5)") (class "Default")
      (node (ref "U1") (pin "5") (pinfunction "PE6_5") (pintype "bidirectional"))
    )
    (net (code "101") (name "unconnected-(U1A-PE7-Pad38)") (class "Default")
      (node (ref "U1") (pin "38") (pinfunction "PE7_38") (pintype "bidirectional"))
    )
    (net (code "102") (name "unconnected-(U1A-PE8-Pad39)") (class "Default")
      (node (ref "U1") (pin "39") (pinfunction "PE8_39") (pintype "bidirectional"))
    )
    (net (code "103") (name "unconnected-(U1A-PE9-Pad40)") (class "Default")
      (node (ref "U1") (pin "40") (pinfunction "PE9_40") (pintype "bidirectional"))
    )
    (net (code "104") (name "unconnected-(U1A-PE10-Pad41)") (class "Default")
      (node (ref "U1") (pin "41") (pinfunction "PE10_41") (pintype "bidirectional"))
    )
    (net (code "105") (name "unconnected-(U1A-PE11-Pad42)") (class "Default")
      (node (ref "U1") (pin "42") (pinfunction "PE11_42") (pintype "bidirectional"))
    )
    (net (code "106") (name "unconnected-(U1A-PE12-Pad43)") (class "Default")
      (node (ref "U1") (pin "43") (pinfunction "PE12_43") (pintype "bidirectional"))
    )
    (net (code "107") (name "unconnected-(U1A-PE13-Pad44)") (class "Default")
      (node (ref "U1") (pin "44") (pinfunction "PE13_44") (pintype "bidirectional"))
    )
    (net (code "108") (name "unconnected-(U1A-PE14-Pad45)") (class "Default")
      (node (ref "U1") (pin "45") (pinfunction "PE14_45") (pintype "bidirectional"))
    )
    (net (code "109") (name "unconnected-(U1A-PE15-Pad46)") (class "Default")
      (node (ref "U1") (pin "46") (pinfunction "PE15_46") (pintype "bidirectional"))
    )
    (net (code "110") (name "unconnected-(U1B-NC-Pad73)") (class "Default")
      (node (ref "U1") (pin "73") (pinfunction "NC_73") (pintype "passive+no_connect"))
    )
    (net (code "111") (name "unconnected-(U5-NC-Pad7)") (class "Default")
      (node (ref "U5") (pin "7") (pinfunction "NC_7") (pintype "passive+no_connect"))
    )
    (net (code "112") (name "unconnected-(U5-NC-Pad8)") (class "Default")
      (node (ref "U5") (pin "8") (pinfunction "NC_8") (pintype "passive+no_connect"))
    )
    (net (code "113") (name "unconnected-(U5-NC-Pad9)") (class "Default")
      (node (ref "U5") (pin "9") (pinfunction "NC_9") (pintype "passive+no_connect"))
    )
    (net (code "114") (name "unconnected-(U5-NC-Pad10)") (class "Default")
      (node (ref "U5") (pin "10") (pinfunction "NC_10") (pintype "passive+no_connect"))
    )
  )
)
